# circuit_design.net
KiCad netlist of a schematic drawn in EAGLE
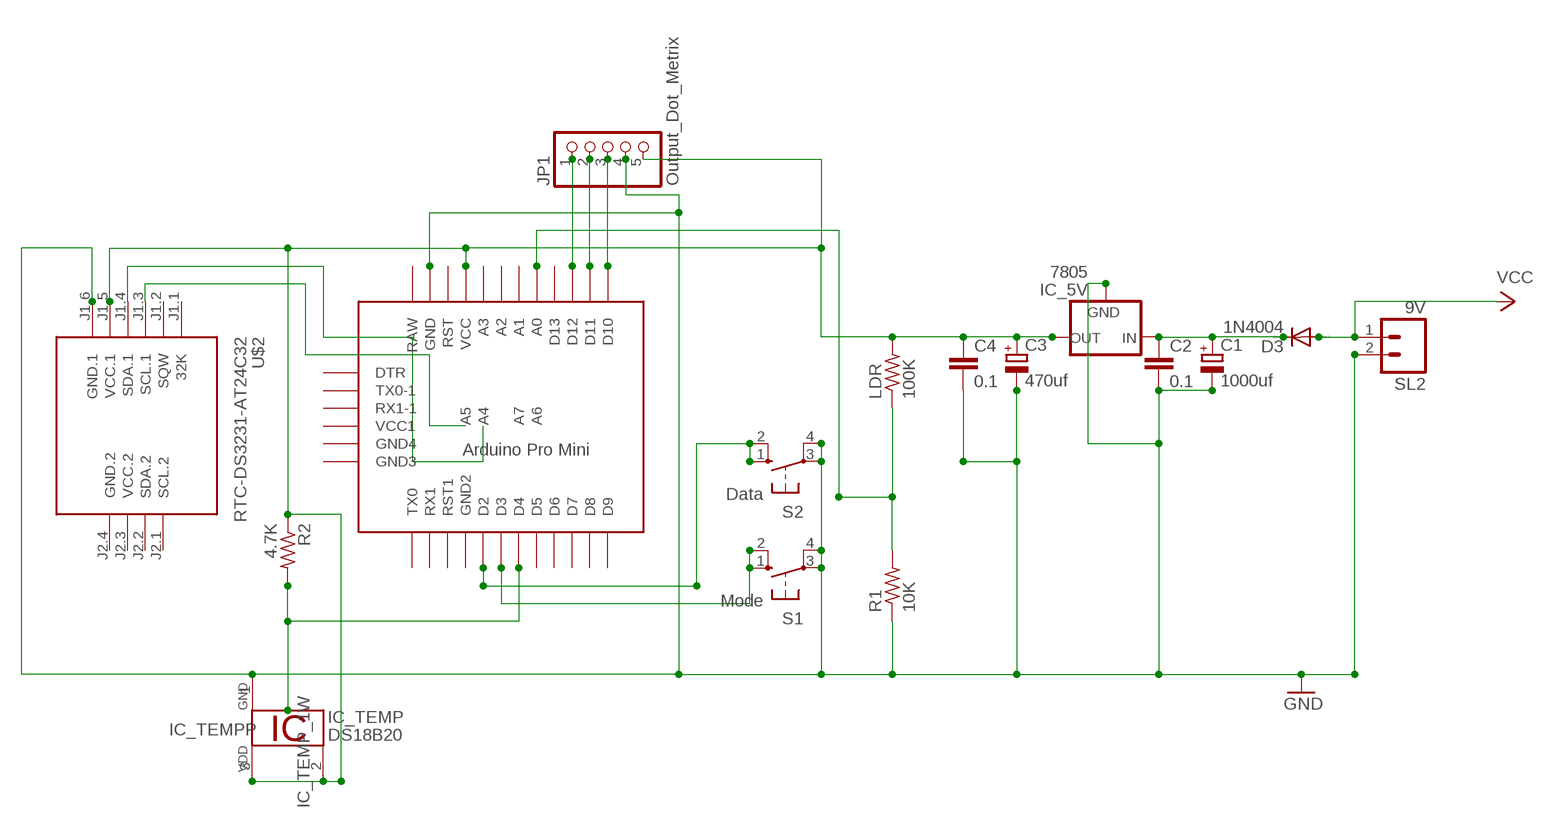
[diagram p0: schematic, sheet 1]

(export (version "E")
  (design (tool "Eeschema 10.0.6"))
  (components
    (comp (ref "C1")
      (value "1000uf")
      (footprint "eagle-import:E2,5-6E")
      (libsource (lib "eagle-import") (part "CPOL-EUE2,5-6E"))
    )
    (comp (ref "C2")
      (value "0.1")
      (footprint "eagle-import:C025-024X044")
      (libsource (lib "eagle-import") (part "C-EU025-024X044"))
    )
    (comp (ref "C3")
      (value "470uf")
      (footprint "eagle-import:E2,5-6E")
      (libsource (lib "eagle-import") (part "CPOL-EUE2,5-6E"))
    )
    (comp (ref "C4")
      (value "0.1")
      (footprint "eagle-import:C025-024X044")
      (libsource (lib "eagle-import") (part "C-EU025-024X044"))
    )
    (comp (ref "D3")
      (value "1N4004")
      (footprint "eagle-import:DO41-10")
      (libsource (lib "eagle-import") (part "1N4004"))
    )
    (comp (ref "IC_5V")
      (value "7805")
      (footprint "eagle-import:78XXS")
      (libsource (lib "eagle-import") (part "78XXS"))
    )
    (comp (ref "IC_TEMP")
      (value "DS18B20")
      (footprint "eagle-import:TO92-")
      (libsource (lib "eagle-import") (part "DS18B20"))
    )
    (comp (ref "JP1")
      (value "Output_Dot_Metrix")
      (footprint "eagle-import:1X05")
      (libsource (lib "eagle-import") (part "PINHD-1X5"))
    )
    (comp (ref "LDR")
      (value "100K")
      (footprint "eagle-import:V526-0")
      (fields (field (name "SPICEPREFIX") "R"))
      (libsource (lib "eagle-import") (part "R-US_V526-0"))
    )
    (comp (ref "R1")
      (value "10K")
      (footprint "eagle-import:0309_12")
      (libsource (lib "eagle-import") (part "R-US_0309/12"))
    )
    (comp (ref "R2")
      (value "4.7K")
      (footprint "eagle-import:0309_12")
      (libsource (lib "eagle-import") (part "R-US_0309/12"))
    )
    (comp (ref "S1")
      (value "Mode")
      (footprint "eagle-import:B3F-10XX")
      (fields (field (name "MPN") "B3F-1000"))
      (libsource (lib "eagle-import") (part "10-XX"))
    )
    (comp (ref "S2")
      (value "Data")
      (footprint "eagle-import:B3F-10XX")
      (fields (field (name "MPN") "B3F-1000"))
      (libsource (lib "eagle-import") (part "10-XX"))
    )
    (comp (ref "SL2")
      (value "9V")
      (footprint "eagle-import:02P")
      (libsource (lib "eagle-import") (part "M02"))
    )
    (comp (ref "U$1")
      (value "PRO-MINI-2")
      (footprint "eagle-import:PRO-MINI-2")
      (libsource (lib "eagle-import") (part "PRO-MINI-2"))
    )
    (comp (ref "U$2")
      (value "RTC-DS3231-AT24C32")
      (footprint "eagle-import:RTC-DS3231-AT24C32")
      (libsource (lib "eagle-import") (part "RTC-DS3231-AT24C32"))
    )
  )
  (nets
    (net (code "1") (name "/GND.2") (class "Default")
      (node (ref "U$2") (pin "J2.4") (pinfunction "GND.2_J2.4") (pintype "power_in"))
    )
    (net (code "2") (name "/VCC.2") (class "Default")
      (node (ref "U$2") (pin "J2.3") (pinfunction "VCC.2_J2.3") (pintype "power_in"))
    )
    (net (code "3") (name "GND") (class "Default")
      (node (ref "C1") (pin "-") (pinfunction "-_-") (pintype "passive"))
      (node (ref "C2") (pin "2") (pinfunction "2_2") (pintype "passive"))
      (node (ref "C3") (pin "-") (pinfunction "-_-") (pintype "passive"))
      (node (ref "C4") (pin "2") (pinfunction "2_2") (pintype "passive"))
      (node (ref "IC_5V") (pin "GND") (pinfunction "GND_GND") (pintype "input"))
      (node (ref "IC_TEMP") (pin "1") (pinfunction "GND_1") (pintype "power_in"))
      (node (ref "JP1") (pin "4") (pinfunction "4_4") (pintype "passive"))
      (node (ref "R1") (pin "1") (pinfunction "1_1") (pintype "passive"))
      (node (ref "S1") (pin "3") (pinfunction "P_3") (pintype "passive"))
      (node (ref "S1") (pin "4") (pinfunction "P1_4") (pintype "passive"))
      (node (ref "S2") (pin "3") (pinfunction "P_3") (pintype "passive"))
      (node (ref "S2") (pin "4") (pinfunction "P1_4") (pintype "passive"))
      (node (ref "SL2") (pin "2") (pinfunction "2_2") (pintype "passive"))
      (node (ref "U$1") (pin "GND") (pinfunction "GND_GND") (pintype "bidirectional"))
      (node (ref "U$2") (pin "J1.6") (pinfunction "GND.1_J1.6") (pintype "power_in"))
    )
    (net (code "4") (name "Net-(C1-Pad+)") (class "Default")
      (node (ref "C1") (pin "+") (pinfunction "+_+") (pintype "passive"))
      (node (ref "C2") (pin "1") (pinfunction "1_1") (pintype "passive"))
      (node (ref "D3") (pin "C") (pinfunction "C_C") (pintype "passive"))
      (node (ref "IC_5V") (pin "IN") (pinfunction "IN_IN") (pintype "input"))
    )
    (net (code "5") (name "Net-(IC_TEMPB-VDD)") (class "Default")
      (node (ref "C3") (pin "+") (pinfunction "+_+") (pintype "passive"))
      (node (ref "C4") (pin "1") (pinfunction "1_1") (pintype "passive"))
      (node (ref "IC_5V") (pin "OUT") (pinfunction "OUT_OUT") (pintype "passive"))
      (node (ref "IC_TEMP") (pin "2") (pinfunction "1W_2") (pintype "power_in"))
      (node (ref "IC_TEMP") (pin "3") (pinfunction "VDD_3") (pintype "power_in"))
      (node (ref "JP1") (pin "5") (pinfunction "5_5") (pintype "passive"))
      (node (ref "LDR") (pin "2") (pinfunction "2_2") (pintype "passive"))
      (node (ref "R2") (pin "1") (pinfunction "1_1") (pintype "passive"))
      (node (ref "U$1") (pin "VCC") (pinfunction "VCC_VCC") (pintype "bidirectional"))
      (node (ref "U$2") (pin "J1.5") (pinfunction "VCC.1_J1.5") (pintype "power_in"))
    )
    (net (code "6") (name "Net-(JP1-Pad1)") (class "Default")
      (node (ref "JP1") (pin "1") (pinfunction "1_1") (pintype "passive"))
      (node (ref "U$1") (pin "D12") (pinfunction "D12_D12") (pintype "bidirectional"))
    )
    (net (code "7") (name "Net-(JP1-Pad2)") (class "Default")
      (node (ref "JP1") (pin "2") (pinfunction "2_2") (pintype "passive"))
      (node (ref "U$1") (pin "D11") (pinfunction "D11_D11") (pintype "bidirectional"))
    )
    (net (code "8") (name "Net-(JP1-Pad3)") (class "Default")
      (node (ref "JP1") (pin "3") (pinfunction "3_3") (pintype "passive"))
      (node (ref "U$1") (pin "D10") (pinfunction "D10_D10") (pintype "bidirectional"))
    )
    (net (code "9") (name "Net-(LDR-Pad1)") (class "Default")
      (node (ref "LDR") (pin "1") (pinfunction "1_1") (pintype "passive"))
      (node (ref "R1") (pin "2") (pinfunction "2_2") (pintype "passive"))
      (node (ref "U$1") (pin "A0") (pinfunction "A0_A0") (pintype "bidirectional"))
    )
    (net (code "10") (name "Net-(R2-Pad2)") (class "Default")
      (node (ref "R2") (pin "2") (pinfunction "2_2") (pintype "passive"))
      (node (ref "U$1") (pin "D4") (pinfunction "D4_D4") (pintype "bidirectional"))
    )
    (net (code "11") (name "Net-(S1-S)") (class "Default")
      (node (ref "S1") (pin "1") (pinfunction "S_1") (pintype "passive"))
      (node (ref "S1") (pin "2") (pinfunction "S1_2") (pintype "passive"))
      (node (ref "U$1") (pin "D3") (pinfunction "D3_D3") (pintype "bidirectional"))
    )
    (net (code "12") (name "Net-(S2-S)") (class "Default")
      (node (ref "S2") (pin "1") (pinfunction "S_1") (pintype "passive"))
      (node (ref "S2") (pin "2") (pinfunction "S1_2") (pintype "passive"))
      (node (ref "U$1") (pin "D2") (pinfunction "D2_D2") (pintype "bidirectional"))
    )
    (net (code "13") (name "VCC") (class "Default")
      (node (ref "D3") (pin "A") (pinfunction "A_A") (pintype "passive"))
      (node (ref "SL2") (pin "1") (pinfunction "1_1") (pintype "passive"))
    )
    (net (code "14") (name "unconnected-(U$1-GND2-PadGND1)") (class "Default")
      (node (ref "U$1") (pin "GND1") (pinfunction "GND2_GND1") (pintype "bidirectional"))
    )
    (net (code "15") (name "unconnected-(U$1-GND3-PadGND2)") (class "Default")
      (node (ref "U$1") (pin "GND2") (pinfunction "GND3_GND2") (pintype "bidirectional"))
    )
    (net (code "16") (name "unconnected-(U$1-GND4-PadGND3)") (class "Default")
      (node (ref "U$1") (pin "GND3") (pinfunction "GND4_GND3") (pintype "bidirectional"))
    )
    (net (code "17") (name "unconnected-(U$1-PadA1)") (class "Default")
      (node (ref "U$1") (pin "A1") (pinfunction "A1_A1") (pintype "bidirectional"))
    )
    (net (code "18") (name "unconnected-(U$1-PadA2)") (class "Default")
      (node (ref "U$1") (pin "A2") (pinfunction "A2_A2") (pintype "bidirectional"))
    )
    (net (code "19") (name "unconnected-(U$1-PadA3)") (class "Default")
      (node (ref "U$1") (pin "A3") (pinfunction "A3_A3") (pintype "bidirectional"))
    )
    (net (code "20") (name "unconnected-(U$1-PadA4)") (class "Default")
      (node (ref "U$1") (pin "A4") (pinfunction "A4_A4") (pintype "bidirectional"))
    )
    (net (code "21") (name "unconnected-(U$1-PadA5)") (class "Default")
      (node (ref "U$1") (pin "A5") (pinfunction "A5_A5") (pintype "bidirectional"))
    )
    (net (code "22") (name "unconnected-(U$1-PadA6)") (class "Default")
      (node (ref "U$1") (pin "A6") (pinfunction "A6_A6") (pintype "bidirectional"))
    )
    (net (code "23") (name "unconnected-(U$1-PadA7)") (class "Default")
      (node (ref "U$1") (pin "A7") (pinfunction "A7_A7") (pintype "bidirectional"))
    )
    (net (code "24") (name "unconnected-(U$1-PadD5)") (class "Default")
      (node (ref "U$1") (pin "D5") (pinfunction "D5_D5") (pintype "bidirectional"))
    )
    (net (code "25") (name "unconnected-(U$1-PadD6)") (class "Default")
      (node (ref "U$1") (pin "D6") (pinfunction "D6_D6") (pintype "bidirectional"))
    )
    (net (code "26") (name "unconnected-(U$1-PadD7)") (class "Default")
      (node (ref "U$1") (pin "D7") (pinfunction "D7_D7") (pintype "bidirectional"))
    )
    (net (code "27") (name "unconnected-(U$1-PadD8)") (class "Default")
      (node (ref "U$1") (pin "D8") (pinfunction "D8_D8") (pintype "bidirectional"))
    )
    (net (code "28") (name "unconnected-(U$1-PadD9)") (class "Default")
      (node (ref "U$1") (pin "D9") (pinfunction "D9_D9") (pintype "bidirectional"))
    )
    (net (code "29") (name "unconnected-(U$1-PadD13)") (class "Default")
      (node (ref "U$1") (pin "D13") (pinfunction "D13_D13") (pintype "bidirectional"))
    )
    (net (code "30") (name "unconnected-(U$1-PadDTR)") (class "Default")
      (node (ref "U$1") (pin "DTR") (pinfunction "DTR_DTR") (pintype "bidirectional"))
    )
    (net (code "31") (name "unconnected-(U$1-PadRAW)") (class "Default")
      (node (ref "U$1") (pin "RAW") (pinfunction "RAW_RAW") (pintype "bidirectional"))
    )
    (net (code "32") (name "unconnected-(U$1-PadRST)") (class "Default")
      (node (ref "U$1") (pin "RST") (pinfunction "RST_RST") (pintype "bidirectional"))
    )
    (net (code "33") (name "unconnected-(U$1-PadRST1)") (class "Default")
      (node (ref "U$1") (pin "RST1") (pinfunction "RST1_RST1") (pintype "bidirectional"))
    )
    (net (code "34") (name "unconnected-(U$1-PadRX1)") (class "Default")
      (node (ref "U$1") (pin "RX1") (pinfunction "RX1_RX1") (pintype "bidirectional"))
    )
    (net (code "35") (name "unconnected-(U$1-PadRX1-1)") (class "Default")
      (node (ref "U$1") (pin "RX1-1") (pinfunction "RX1-1_RX1-1") (pintype "bidirectional"))
    )
    (net (code "36") (name "unconnected-(U$1-PadTX0)") (class "Default")
      (node (ref "U$1") (pin "TX0") (pinfunction "TX0_TX0") (pintype "bidirectional"))
    )
    (net (code "37") (name "unconnected-(U$1-PadTX0-1)") (class "Default")
      (node (ref "U$1") (pin "TX0-1") (pinfunction "TX0-1_TX0-1") (pintype "bidirectional"))
    )
    (net (code "38") (name "unconnected-(U$1-PadVCC1)") (class "Default")
      (node (ref "U$1") (pin "VCC1") (pinfunction "VCC1_VCC1") (pintype "bidirectional"))
    )
    (net (code "39") (name "unconnected-(U$2-32K-PadJ1.1)") (class "Default")
      (node (ref "U$2") (pin "J1.1") (pinfunction "32K_J1.1") (pintype "bidirectional"))
    )
    (net (code "40") (name "unconnected-(U$2-SCL.1-PadJ1.3)") (class "Default")
      (node (ref "U$2") (pin "J1.3") (pinfunction "SCL.1_J1.3") (pintype "bidirectional"))
    )
    (net (code "41") (name "unconnected-(U$2-SCL.2-PadJ2.1)") (class "Default")
      (node (ref "U$2") (pin "J2.1") (pinfunction "SCL.2_J2.1") (pintype "bidirectional"))
    )
    (net (code "42") (name "unconnected-(U$2-SDA.1-PadJ1.4)") (class "Default")
      (node (ref "U$2") (pin "J1.4") (pinfunction "SDA.1_J1.4") (pintype "bidirectional"))
    )
    (net (code "43") (name "unconnected-(U$2-SDA.2-PadJ2.2)") (class "Default")
      (node (ref "U$2") (pin "J2.2") (pinfunction "SDA.2_J2.2") (pintype "bidirectional"))
    )
    (net (code "44") (name "unconnected-(U$2-SQW-PadJ1.2)") (class "Default")
      (node (ref "U$2") (pin "J1.2") (pinfunction "SQW_J1.2") (pintype "bidirectional"))
    )
  )
)
